# Keypad_Arduino_Uno_Shield.net
KiCad netlist of a schematic drawn in EAGLE
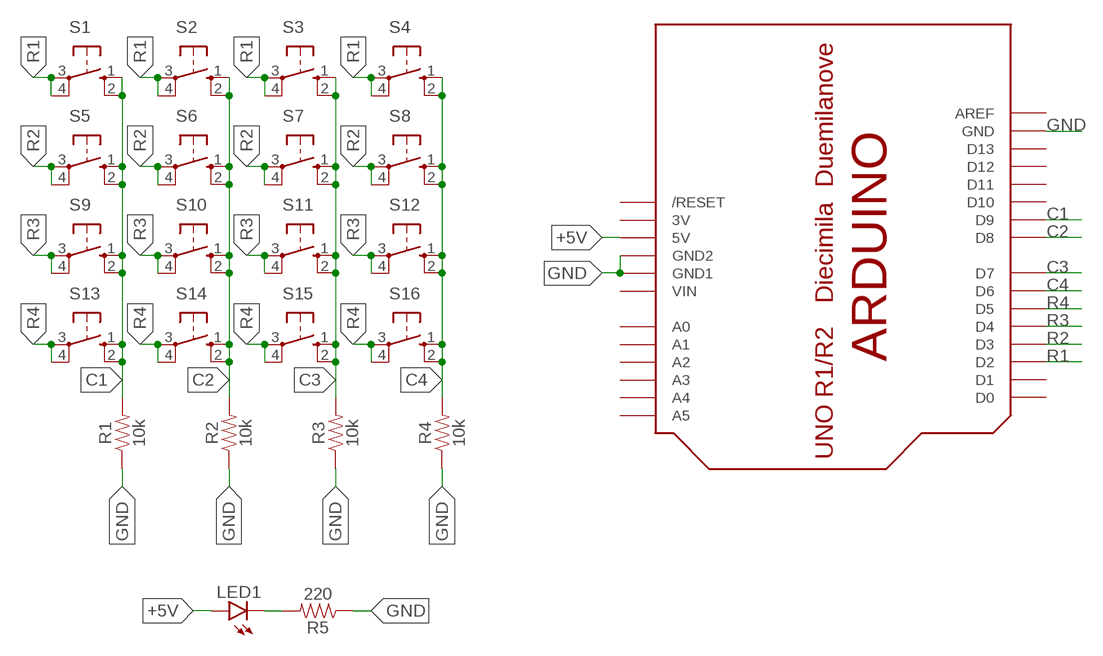
[diagram p0: schematic, sheet 1]

(export (version "E")
  (design (tool "Eeschema 10.0.6"))
  (components
    (comp (ref "LED1")
      (value "LEDSML0805")
      (footprint "eagle-import:SML0805")
      (libsource (lib "eagle-import") (part "LEDSML0805"))
    )
    (comp (ref "R1")
      (value "10k")
      (footprint "eagle-import:1206")
      (libsource (lib "eagle-import") (part "RESISTOR1206"))
    )
    (comp (ref "R2")
      (value "10k")
      (footprint "eagle-import:1206")
      (libsource (lib "eagle-import") (part "RESISTOR1206"))
    )
    (comp (ref "R3")
      (value "10k")
      (footprint "eagle-import:1206")
      (libsource (lib "eagle-import") (part "RESISTOR1206"))
    )
    (comp (ref "R4")
      (value "10k")
      (footprint "eagle-import:1206")
      (libsource (lib "eagle-import") (part "RESISTOR1206"))
    )
    (comp (ref "R5")
      (value "220")
      (footprint "eagle-import:1206")
      (libsource (lib "eagle-import") (part "RESISTOR1206"))
    )
    (comp (ref "S1")
      (value "10-XX")
      (footprint "eagle-import:B3F-10XX")
      (fields (field (name "MPN") "B3F-1000"))
      (libsource (lib "eagle-import") (part "10-XX"))
    )
    (comp (ref "S2")
      (value "10-XX")
      (footprint "eagle-import:B3F-10XX")
      (fields (field (name "MPN") "B3F-1000"))
      (libsource (lib "eagle-import") (part "10-XX"))
    )
    (comp (ref "S3")
      (value "10-XX")
      (footprint "eagle-import:B3F-10XX")
      (fields (field (name "MPN") "B3F-1000"))
      (libsource (lib "eagle-import") (part "10-XX"))
    )
    (comp (ref "S4")
      (value "10-XX")
      (footprint "eagle-import:B3F-10XX")
      (fields (field (name "MPN") "B3F-1000"))
      (libsource (lib "eagle-import") (part "10-XX"))
    )
    (comp (ref "S5")
      (value "10-XX")
      (footprint "eagle-import:B3F-10XX")
      (fields (field (name "MPN") "B3F-1000"))
      (libsource (lib "eagle-import") (part "10-XX"))
    )
    (comp (ref "S6")
      (value "10-XX")
      (footprint "eagle-import:B3F-10XX")
      (fields (field (name "MPN") "B3F-1000"))
      (libsource (lib "eagle-import") (part "10-XX"))
    )
    (comp (ref "S7")
      (value "10-XX")
      (footprint "eagle-import:B3F-10XX")
      (fields (field (name "MPN") "B3F-1000"))
      (libsource (lib "eagle-import") (part "10-XX"))
    )
    (comp (ref "S8")
      (value "10-XX")
      (footprint "eagle-import:B3F-10XX")
      (fields (field (name "MPN") "B3F-1000"))
      (libsource (lib "eagle-import") (part "10-XX"))
    )
    (comp (ref "S9")
      (value "10-XX")
      (footprint "eagle-import:B3F-10XX")
      (fields (field (name "MPN") "B3F-1000"))
      (libsource (lib "eagle-import") (part "10-XX"))
    )
    (comp (ref "S10")
      (value "10-XX")
      (footprint "eagle-import:B3F-10XX")
      (fields (field (name "MPN") "B3F-1000"))
      (libsource (lib "eagle-import") (part "10-XX"))
    )
    (comp (ref "S11")
      (value "10-XX")
      (footprint "eagle-import:B3F-10XX")
      (fields (field (name "MPN") "B3F-1000"))
      (libsource (lib "eagle-import") (part "10-XX"))
    )
    (comp (ref "S12")
      (value "10-XX")
      (footprint "eagle-import:B3F-10XX")
      (fields (field (name "MPN") "B3F-1000"))
      (libsource (lib "eagle-import") (part "10-XX"))
    )
    (comp (ref "S13")
      (value "10-XX")
      (footprint "eagle-import:B3F-10XX")
      (fields (field (name "MPN") "B3F-1000"))
      (libsource (lib "eagle-import") (part "10-XX"))
    )
    (comp (ref "S14")
      (value "10-XX")
      (footprint "eagle-import:B3F-10XX")
      (fields (field (name "MPN") "B3F-1000"))
      (libsource (lib "eagle-import") (part "10-XX"))
    )
    (comp (ref "S15")
      (value "10-XX")
      (footprint "eagle-import:B3F-10XX")
      (fields (field (name "MPN") "B3F-1000"))
      (libsource (lib "eagle-import") (part "10-XX"))
    )
    (comp (ref "S16")
      (value "10-XX")
      (footprint "eagle-import:B3F-10XX")
      (fields (field (name "MPN") "B3F-1000"))
      (libsource (lib "eagle-import") (part "10-XX"))
    )
    (comp (ref "U$1")
      (value "ARDUINOUNO")
      (footprint "eagle-import:ARDUINO")
      (libsource (lib "eagle-import") (part "ARDUINOUNO"))
    )
  )
  (nets
    (net (code "1") (name "+5V") (class "Default")
      (node (ref "LED1") (pin "A") (pinfunction "A_A") (pintype "passive"))
      (node (ref "U$1") (pin "5V") (pinfunction "5V_5V") (pintype "power_in"))
    )
    (net (code "2") (name "/3V") (class "Default")
      (node (ref "U$1") (pin "3V") (pinfunction "3V_3V") (pintype "power_in"))
    )
    (net (code "3") (name "/VIN") (class "Default")
      (node (ref "U$1") (pin "VIN") (pinfunction "VIN_VIN") (pintype "power_in"))
    )
    (net (code "4") (name "C1") (class "Default")
      (node (ref "R1") (pin "2") (pinfunction "2_2") (pintype "passive"))
      (node (ref "S1") (pin "1") (pinfunction "S_1") (pintype "passive"))
      (node (ref "S1") (pin "2") (pinfunction "S1_2") (pintype "passive"))
      (node (ref "S13") (pin "1") (pinfunction "S_1") (pintype "passive"))
      (node (ref "S13") (pin "2") (pinfunction "S1_2") (pintype "passive"))
      (node (ref "S5") (pin "1") (pinfunction "S_1") (pintype "passive"))
      (node (ref "S5") (pin "2") (pinfunction "S1_2") (pintype "passive"))
      (node (ref "S9") (pin "1") (pinfunction "S_1") (pintype "passive"))
      (node (ref "S9") (pin "2") (pinfunction "S1_2") (pintype "passive"))
      (node (ref "U$1") (pin "D9") (pinfunction "D9_D9") (pintype "bidirectional"))
    )
    (net (code "5") (name "C2") (class "Default")
      (node (ref "R2") (pin "2") (pinfunction "2_2") (pintype "passive"))
      (node (ref "S10") (pin "1") (pinfunction "S_1") (pintype "passive"))
      (node (ref "S10") (pin "2") (pinfunction "S1_2") (pintype "passive"))
      (node (ref "S14") (pin "1") (pinfunction "S_1") (pintype "passive"))
      (node (ref "S14") (pin "2") (pinfunction "S1_2") (pintype "passive"))
      (node (ref "S2") (pin "1") (pinfunction "S_1") (pintype "passive"))
      (node (ref "S2") (pin "2") (pinfunction "S1_2") (pintype "passive"))
      (node (ref "S6") (pin "1") (pinfunction "S_1") (pintype "passive"))
      (node (ref "S6") (pin "2") (pinfunction "S1_2") (pintype "passive"))
      (node (ref "U$1") (pin "D8") (pinfunction "D8_D8") (pintype "bidirectional"))
    )
    (net (code "6") (name "C3") (class "Default")
      (node (ref "R3") (pin "2") (pinfunction "2_2") (pintype "passive"))
      (node (ref "S11") (pin "1") (pinfunction "S_1") (pintype "passive"))
      (node (ref "S11") (pin "2") (pinfunction "S1_2") (pintype "passive"))
      (node (ref "S15") (pin "1") (pinfunction "S_1") (pintype "passive"))
      (node (ref "S15") (pin "2") (pinfunction "S1_2") (pintype "passive"))
      (node (ref "S3") (pin "1") (pinfunction "S_1") (pintype "passive"))
      (node (ref "S3") (pin "2") (pinfunction "S1_2") (pintype "passive"))
      (node (ref "S7") (pin "1") (pinfunction "S_1") (pintype "passive"))
      (node (ref "S7") (pin "2") (pinfunction "S1_2") (pintype "passive"))
      (node (ref "U$1") (pin "D7") (pinfunction "D7_D7") (pintype "bidirectional"))
    )
    (net (code "7") (name "C4") (class "Default")
      (node (ref "R4") (pin "2") (pinfunction "2_2") (pintype "passive"))
      (node (ref "S12") (pin "1") (pinfunction "S_1") (pintype "passive"))
      (node (ref "S12") (pin "2") (pinfunction "S1_2") (pintype "passive"))
      (node (ref "S16") (pin "1") (pinfunction "S_1") (pintype "passive"))
      (node (ref "S16") (pin "2") (pinfunction "S1_2") (pintype "passive"))
      (node (ref "S4") (pin "1") (pinfunction "S_1") (pintype "passive"))
      (node (ref "S4") (pin "2") (pinfunction "S1_2") (pintype "passive"))
      (node (ref "S8") (pin "1") (pinfunction "S_1") (pintype "passive"))
      (node (ref "S8") (pin "2") (pinfunction "S1_2") (pintype "passive"))
      (node (ref "U$1") (pin "D6") (pinfunction "D6_D6") (pintype "bidirectional"))
    )
    (net (code "8") (name "GND") (class "Default")
      (node (ref "R1") (pin "1") (pinfunction "1_1") (pintype "passive"))
      (node (ref "R2") (pin "1") (pinfunction "1_1") (pintype "passive"))
      (node (ref "R3") (pin "1") (pinfunction "1_1") (pintype "passive"))
      (node (ref "R4") (pin "1") (pinfunction "1_1") (pintype "passive"))
      (node (ref "R5") (pin "1") (pinfunction "1_1") (pintype "passive"))
      (node (ref "U$1") (pin "GND") (pinfunction "GND_GND") (pintype "power_in"))
      (node (ref "U$1") (pin "GND1") (pinfunction "GND1_GND1") (pintype "power_in"))
      (node (ref "U$1") (pin "GND2") (pinfunction "GND2_GND2") (pintype "power_in"))
    )
    (net (code "9") (name "Net-(LED1-PadC)") (class "Default")
      (node (ref "LED1") (pin "C") (pinfunction "C_C") (pintype "passive"))
      (node (ref "R5") (pin "2") (pinfunction "2_2") (pintype "passive"))
    )
    (net (code "10") (name "R1") (class "Default")
      (node (ref "S1") (pin "3") (pinfunction "P_3") (pintype "passive"))
      (node (ref "S1") (pin "4") (pinfunction "P1_4") (pintype "passive"))
      (node (ref "S2") (pin "3") (pinfunction "P_3") (pintype "passive"))
      (node (ref "S2") (pin "4") (pinfunction "P1_4") (pintype "passive"))
      (node (ref "S3") (pin "3") (pinfunction "P_3") (pintype "passive"))
      (node (ref "S3") (pin "4") (pinfunction "P1_4") (pintype "passive"))
      (node (ref "S4") (pin "3") (pinfunction "P_3") (pintype "passive"))
      (node (ref "S4") (pin "4") (pinfunction "P1_4") (pintype "passive"))
      (node (ref "U$1") (pin "D2") (pinfunction "D2_D2") (pintype "bidirectional"))
    )
    (net (code "11") (name "R2") (class "Default")
      (node (ref "S5") (pin "3") (pinfunction "P_3") (pintype "passive"))
      (node (ref "S5") (pin "4") (pinfunction "P1_4") (pintype "passive"))
      (node (ref "S6") (pin "3") (pinfunction "P_3") (pintype "passive"))
      (node (ref "S6") (pin "4") (pinfunction "P1_4") (pintype "passive"))
      (node (ref "S7") (pin "3") (pinfunction "P_3") (pintype "passive"))
      (node (ref "S7") (pin "4") (pinfunction "P1_4") (pintype "passive"))
      (node (ref "S8") (pin "3") (pinfunction "P_3") (pintype "passive"))
      (node (ref "S8") (pin "4") (pinfunction "P1_4") (pintype "passive"))
      (node (ref "U$1") (pin "D3") (pinfunction "D3_D3") (pintype "bidirectional"))
    )
    (net (code "12") (name "R3") (class "Default")
      (node (ref "S10") (pin "3") (pinfunction "P_3") (pintype "passive"))
      (node (ref "S10") (pin "4") (pinfunction "P1_4") (pintype "passive"))
      (node (ref "S11") (pin "3") (pinfunction "P_3") (pintype "passive"))
      (node (ref "S11") (pin "4") (pinfunction "P1_4") (pintype "passive"))
      (node (ref "S12") (pin "3") (pinfunction "P_3") (pintype "passive"))
      (node (ref "S12") (pin "4") (pinfunction "P1_4") (pintype "passive"))
      (node (ref "S9") (pin "3") (pinfunction "P_3") (pintype "passive"))
      (node (ref "S9") (pin "4") (pinfunction "P1_4") (pintype "passive"))
      (node (ref "U$1") (pin "D4") (pinfunction "D4_D4") (pintype "bidirectional"))
    )
    (net (code "13") (name "R4") (class "Default")
      (node (ref "S13") (pin "3") (pinfunction "P_3") (pintype "passive"))
      (node (ref "S13") (pin "4") (pinfunction "P1_4") (pintype "passive"))
      (node (ref "S14") (pin "3") (pinfunction "P_3") (pintype "passive"))
      (node (ref "S14") (pin "4") (pinfunction "P1_4") (pintype "passive"))
      (node (ref "S15") (pin "3") (pinfunction "P_3") (pintype "passive"))
      (node (ref "S15") (pin "4") (pinfunction "P1_4") (pintype "passive"))
      (node (ref "S16") (pin "3") (pinfunction "P_3") (pintype "passive"))
      (node (ref "S16") (pin "4") (pinfunction "P1_4") (pintype "passive"))
      (node (ref "U$1") (pin "D5") (pinfunction "D5_D5") (pintype "bidirectional"))
    )
    (net (code "14") (name "unconnected-(U$1-PadA0)") (class "Default")
      (node (ref "U$1") (pin "A0") (pinfunction "A0_A0") (pintype "bidirectional"))
    )
    (net (code "15") (name "unconnected-(U$1-PadA1)") (class "Default")
      (node (ref "U$1") (pin "A1") (pinfunction "A1_A1") (pintype "bidirectional"))
    )
    (net (code "16") (name "unconnected-(U$1-PadA2)") (class "Default")
      (node (ref "U$1") (pin "A2") (pinfunction "A2_A2") (pintype "bidirectional"))
    )
    (net (code "17") (name "unconnected-(U$1-PadA3)") (class "Default")
      (node (ref "U$1") (pin "A3") (pinfunction "A3_A3") (pintype "bidirectional"))
    )
    (net (code "18") (name "unconnected-(U$1-PadA4)") (class "Default")
      (node (ref "U$1") (pin "A4") (pinfunction "A4_A4") (pintype "bidirectional"))
    )
    (net (code "19") (name "unconnected-(U$1-PadA5)") (class "Default")
      (node (ref "U$1") (pin "A5") (pinfunction "A5_A5") (pintype "bidirectional"))
    )
    (net (code "20") (name "unconnected-(U$1-PadAREF)") (class "Default")
      (node (ref "U$1") (pin "AREF") (pinfunction "AREF_AREF") (pintype "bidirectional"))
    )
    (net (code "21") (name "unconnected-(U$1-PadD0)") (class "Default")
      (node (ref "U$1") (pin "D0") (pinfunction "D0_D0") (pintype "bidirectional"))
    )
    (net (code "22") (name "unconnected-(U$1-PadD1)") (class "Default")
      (node (ref "U$1") (pin "D1") (pinfunction "D1_D1") (pintype "bidirectional"))
    )
    (net (code "23") (name "unconnected-(U$1-PadD10)") (class "Default")
      (node (ref "U$1") (pin "D10") (pinfunction "D10_D10") (pintype "bidirectional"))
    )
    (net (code "24") (name "unconnected-(U$1-PadD11)") (class "Default")
      (node (ref "U$1") (pin "D11") (pinfunction "D11_D11") (pintype "bidirectional"))
    )
    (net (code "25") (name "unconnected-(U$1-PadD12)") (class "Default")
      (node (ref "U$1") (pin "D12") (pinfunction "D12_D12") (pintype "bidirectional"))
    )
    (net (code "26") (name "unconnected-(U$1-PadD13)") (class "Default")
      (node (ref "U$1") (pin "D13") (pinfunction "D13_D13") (pintype "bidirectional"))
    )
    (net (code "27") (name "unconnected-(U$1-{slash}RESET-PadRESET)") (class "Default")
      (node (ref "U$1") (pin "RESET") (pinfunction "/RESET_RESET") (pintype "bidirectional"))
    )
  )
)
